# SomTest1.net
KiCad netlist of a schematic drawn in EAGLE
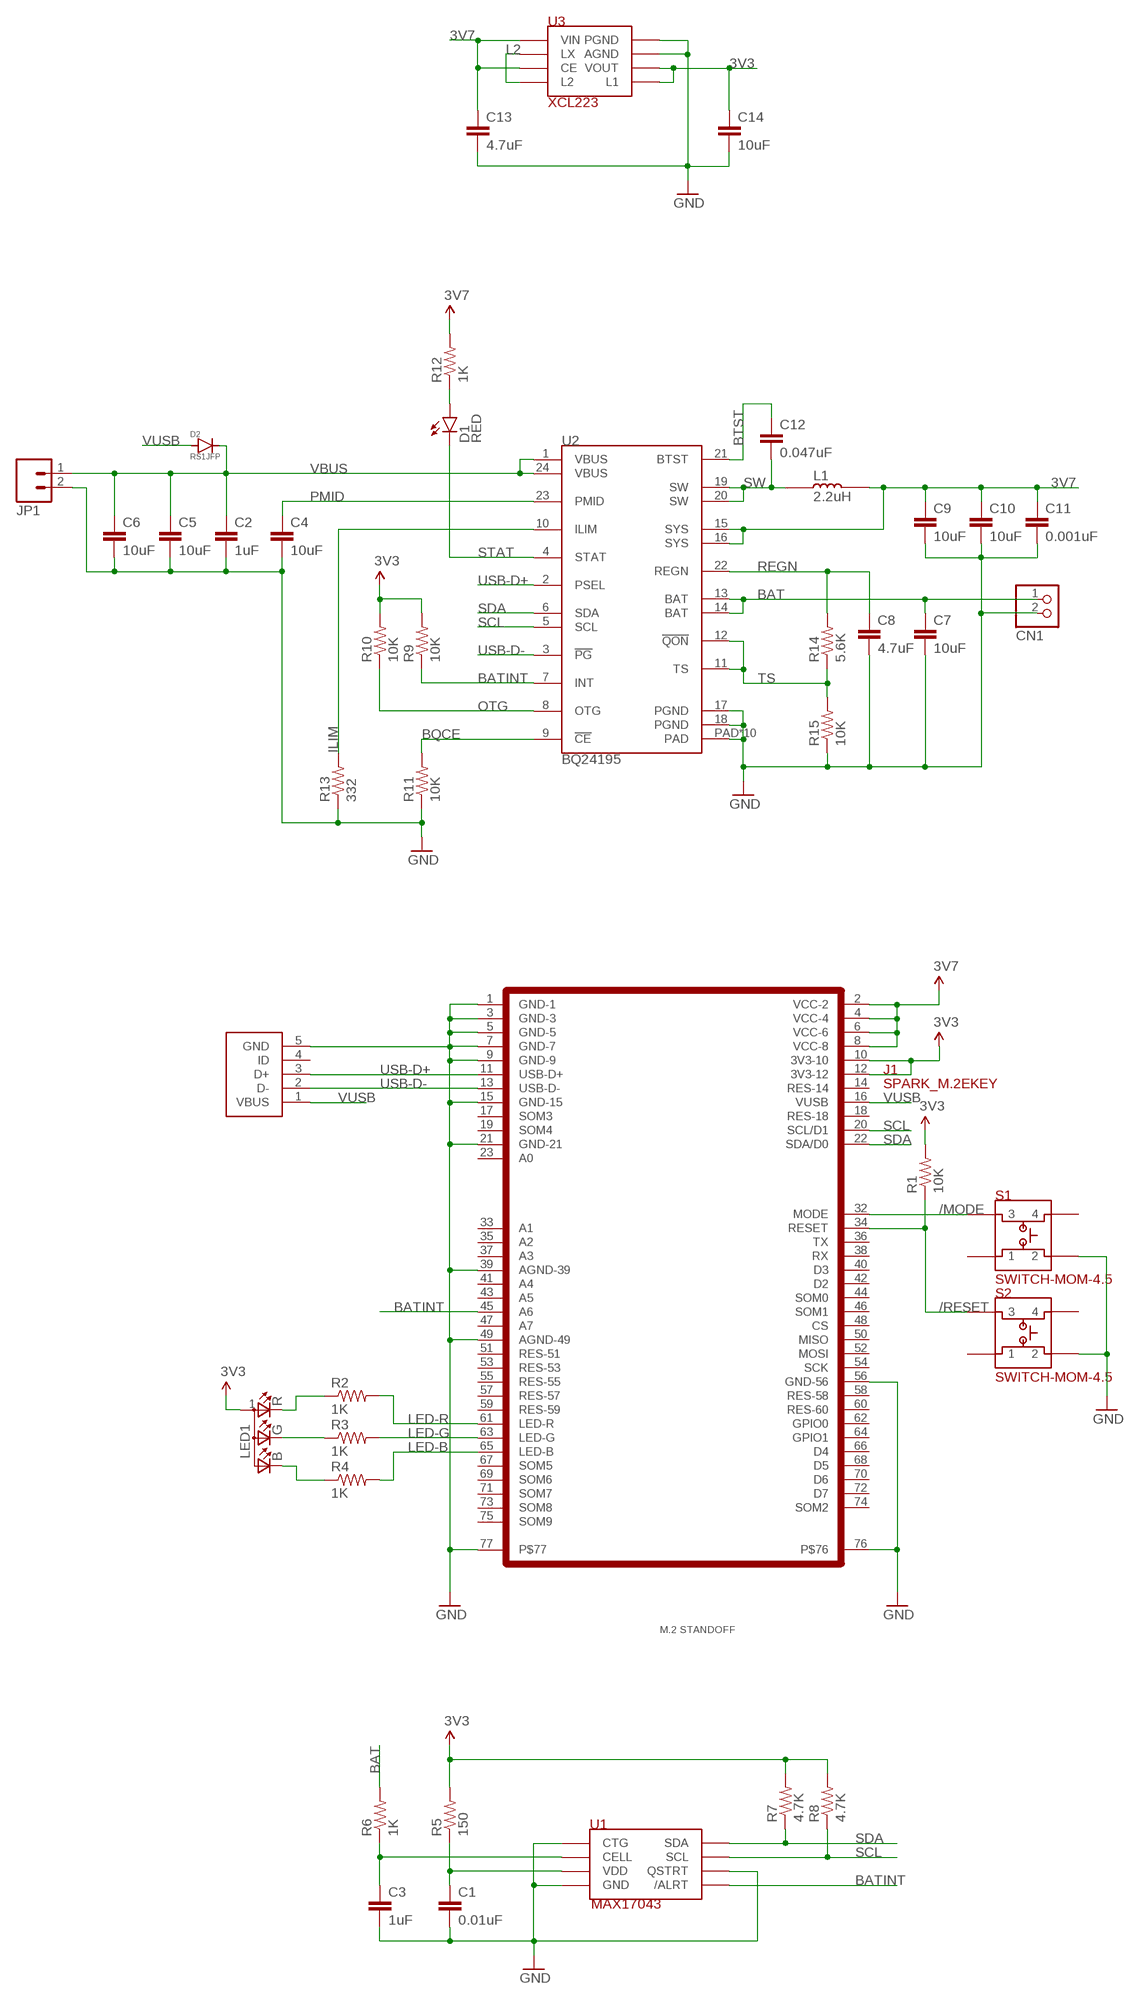
[diagram p0: schematic, sheet 1]

(export (version "E")
  (design (tool "Eeschema 10.0.6"))
  (components
    (comp (ref "C1")
      (value "0.01uF")
      (footprint "eagle-import:0603-CAP")
      (libsource (lib "eagle-import") (part "CAP-0.01UF-0603"))
    )
    (comp (ref "C2")
      (value "1uF")
      (footprint "eagle-import:0603-CAP")
      (libsource (lib "eagle-import") (part "CAP-1UF-0603.DEV"))
    )
    (comp (ref "C3")
      (value "1uF")
      (footprint "eagle-import:0603-CAP")
      (libsource (lib "eagle-import") (part "CAP-1UF-0603.DEV"))
    )
    (comp (ref "C4")
      (value "10uF")
      (footprint "eagle-import:0603-CAP")
      (libsource (lib "eagle-import") (part "CAP-10UF-0603"))
    )
    (comp (ref "C5")
      (value "10uF")
      (footprint "eagle-import:0603-CAP")
      (libsource (lib "eagle-import") (part "CAP-10UF-0603"))
    )
    (comp (ref "C6")
      (value "10uF")
      (footprint "eagle-import:0603-CAP")
      (libsource (lib "eagle-import") (part "CAP-10UF-0603"))
    )
    (comp (ref "C7")
      (value "10uF")
      (footprint "eagle-import:0603-CAP")
      (libsource (lib "eagle-import") (part "CAP-10UF-0603"))
    )
    (comp (ref "C8")
      (value "4.7uF")
      (footprint "eagle-import:0603-CAP")
      (libsource (lib "eagle-import") (part "CAP-4.7UF-0603"))
    )
    (comp (ref "C9")
      (value "10uF")
      (footprint "eagle-import:0603-CAP")
      (libsource (lib "eagle-import") (part "CAP-10UF-0603"))
    )
    (comp (ref "C10")
      (value "10uF")
      (footprint "eagle-import:0603-CAP")
      (libsource (lib "eagle-import") (part "CAP-10UF-0603"))
    )
    (comp (ref "C11")
      (value "0.001uF")
      (footprint "eagle-import:0603-CAP")
      (libsource (lib "eagle-import") (part "CAP-0.001UF-0603"))
    )
    (comp (ref "C12")
      (value "0.047uF")
      (footprint "eagle-import:0603-CAP")
      (libsource (lib "eagle-import") (part "CAP-0.047UF-0603"))
    )
    (comp (ref "C13")
      (value "4.7uF")
      (footprint "eagle-import:0603-CAP")
      (libsource (lib "eagle-import") (part "CAP-4.7UF-0603"))
    )
    (comp (ref "C14")
      (value "10uF")
      (footprint "eagle-import:0603-CAP")
      (libsource (lib "eagle-import") (part "CAP-10UF-0603"))
    )
    (comp (ref "CN1")
      (value "JST_2PIN-THM")
      (footprint "eagle-import:JST-PH-2-THM")
      (libsource (lib "eagle-import") (part "JST_2PIN-THM"))
    )
    (comp (ref "D1")
      (value "RED")
      (footprint "eagle-import:LED-0603")
      (libsource (lib "eagle-import") (part "LED-RED"))
    )
    (comp (ref "D2")
      (value "RS1JFP")
      (footprint "eagle-import:SOD-123HE-ON")
      (libsource (lib "eagle-import") (part "DIODE-RS1JFP"))
    )
    (comp (ref "J1")
      (value "SPARK_M.2EKEY")
      (footprint "eagle-import:SPARK_M.2EKEY-LESS-CREAM")
      (libsource (lib "eagle-import") (part "SPARK_M.2EKEY"))
    )
    (comp (ref "JP1")
      (value "M02PTH")
      (footprint "eagle-import:1X02")
      (libsource (lib "eagle-import") (part "M02PTH"))
    )
    (comp (ref "L1")
      (value "2.2uH")
      (footprint "eagle-import:1008-BOURNS")
      (libsource (lib "eagle-import") (part "INDUCTOR-2.2UH"))
    )
    (comp (ref "LED1")
      (value "LED-RGB-CREE-SMD")
      (footprint "eagle-import:LED-RGB-CREE-SMD")
      (libsource (lib "eagle-import") (part "LED-RGB-CREE-SMD"))
    )
    (comp (ref "R1")
      (value "10K")
      (footprint "eagle-import:0603-RES")
      (libsource (lib "eagle-import") (part "RES-10K-06030603"))
    )
    (comp (ref "R2")
      (value "1K")
      (footprint "eagle-import:0603-RES")
      (libsource (lib "eagle-import") (part "RES-1K-0603"))
    )
    (comp (ref "R3")
      (value "1K")
      (footprint "eagle-import:0603-RES")
      (libsource (lib "eagle-import") (part "RES-1K-0603"))
    )
    (comp (ref "R4")
      (value "1K")
      (footprint "eagle-import:0603-RES")
      (libsource (lib "eagle-import") (part "RES-1K-0603"))
    )
    (comp (ref "R5")
      (value "150")
      (footprint "eagle-import:0603-RES")
      (libsource (lib "eagle-import") (part "RES-150-0603"))
    )
    (comp (ref "R6")
      (value "1K")
      (footprint "eagle-import:0603-RES")
      (libsource (lib "eagle-import") (part "RES-1K-0603"))
    )
    (comp (ref "R7")
      (value "4.7K")
      (footprint "eagle-import:0603-RES")
      (libsource (lib "eagle-import") (part "RES-4.7K-0603"))
    )
    (comp (ref "R8")
      (value "4.7K")
      (footprint "eagle-import:0603-RES")
      (libsource (lib "eagle-import") (part "RES-4.7K-0603"))
    )
    (comp (ref "R9")
      (value "10K")
      (footprint "eagle-import:0603-RES")
      (libsource (lib "eagle-import") (part "RES-10K-06030603"))
    )
    (comp (ref "R10")
      (value "10K")
      (footprint "eagle-import:0603-RES")
      (libsource (lib "eagle-import") (part "RES-10K-06030603"))
    )
    (comp (ref "R11")
      (value "10K")
      (footprint "eagle-import:0603-RES")
      (libsource (lib "eagle-import") (part "RES-10K-06030603"))
    )
    (comp (ref "R12")
      (value "1K")
      (footprint "eagle-import:0603-RES")
      (libsource (lib "eagle-import") (part "RES-1K-0603"))
    )
    (comp (ref "R13")
      (value "332")
      (footprint "eagle-import:0603-RES")
      (libsource (lib "eagle-import") (part "RES-332-0603.DEV"))
    )
    (comp (ref "R14")
      (value "5.6K")
      (footprint "eagle-import:0603-RES")
      (libsource (lib "eagle-import") (part "RES-5.6K-0603"))
    )
    (comp (ref "R15")
      (value "10K")
      (footprint "eagle-import:0603-RES")
      (libsource (lib "eagle-import") (part "RES-10K-06030603"))
    )
    (comp (ref "S1")
      (value "SWITCH-MOM-4.5")
      (footprint "eagle-import:SWITCH-MOM-4.5")
      (libsource (lib "eagle-import") (part "SWITCH-MOM-4.5"))
    )
    (comp (ref "S2")
      (value "SWITCH-MOM-4.5")
      (footprint "eagle-import:SWITCH-MOM-4.5")
      (libsource (lib "eagle-import") (part "SWITCH-MOM-4.5"))
    )
    (comp (ref "U$1")
      (value "M2-STANDOFF")
      (footprint "eagle-import:M2-STANDOFF")
      (libsource (lib "eagle-import") (part "M2-STANDOFF"))
    )
    (comp (ref "U$3")
      (value "USB-MICRO-B-SOCKET-AMPHENOL")
      (footprint "eagle-import:USB-B-SMT-AMPHENOL")
      (libsource (lib "eagle-import") (part "USB-MICRO-B-SOCKET-AMPHENOL"))
    )
    (comp (ref "U1")
      (value "MAX17043")
      (footprint "eagle-import:9UCSP-MAXIM")
      (libsource (lib "eagle-import") (part "MAX17043"))
    )
    (comp (ref "U2")
      (value "BQ24195")
      (footprint "eagle-import:24VFQN-TI")
      (libsource (lib "eagle-import") (part "BQ24195"))
    )
    (comp (ref "U3")
      (value "XCL223")
      (footprint "eagle-import:REG-XCL223-LESS-CREAM")
      (libsource (lib "eagle-import") (part "REG-XCL223"))
    )
  )
  (nets
    (net (code "1") (name "/BAT") (class "Default")
      (node (ref "C7") (pin "1") (pinfunction "1_1") (pintype "passive"))
      (node (ref "CN1") (pin "1") (pinfunction "2_1") (pintype "passive"))
      (node (ref "R6") (pin "2") (pinfunction "2_2") (pintype "passive"))
      (node (ref "U2") (pin "13") (pinfunction "BAT_13") (pintype "passive"))
      (node (ref "U2") (pin "14") (pinfunction "BAT_14") (pintype "power_in"))
    )
    (net (code "2") (name "/BATINT") (class "Default")
      (node (ref "J1") (pin "45") (pinfunction "A6_45") (pintype "bidirectional"))
      (node (ref "R9") (pin "1") (pinfunction "1_1") (pintype "passive"))
      (node (ref "U1") (pin "C1") (pinfunction "/ALRT_C1") (pintype "output"))
      (node (ref "U2") (pin "7") (pinfunction "INT_7") (pintype "bidirectional"))
    )
    (net (code "3") (name "/BQCE") (class "Default")
      (node (ref "R11") (pin "2") (pinfunction "2_2") (pintype "passive"))
      (node (ref "U2") (pin "9") (pinfunction "~{CE}_9") (pintype "output"))
    )
    (net (code "4") (name "/BTST") (class "Default")
      (node (ref "C12") (pin "1") (pinfunction "1_1") (pintype "passive"))
      (node (ref "U2") (pin "21") (pinfunction "BTST_21") (pintype "bidirectional"))
    )
    (net (code "5") (name "/ILIM") (class "Default")
      (node (ref "R13") (pin "2") (pinfunction "2_2") (pintype "passive"))
      (node (ref "U2") (pin "10") (pinfunction "ILIM_10") (pintype "output"))
    )
    (net (code "6") (name "/L2") (class "Default")
      (node (ref "U3") (pin "5") (pinfunction "LX_5") (pintype "passive"))
      (node (ref "U3") (pin "8") (pinfunction "L2_8") (pintype "passive"))
    )
    (net (code "7") (name "/LED-B") (class "Default")
      (node (ref "J1") (pin "65") (pinfunction "LED-B_65") (pintype "bidirectional"))
      (node (ref "R4") (pin "2") (pinfunction "2_2") (pintype "passive"))
    )
    (net (code "8") (name "/LED-G") (class "Default")
      (node (ref "J1") (pin "63") (pinfunction "LED-G_63") (pintype "bidirectional"))
      (node (ref "R3") (pin "2") (pinfunction "2_2") (pintype "passive"))
    )
    (net (code "9") (name "/LED-R") (class "Default")
      (node (ref "J1") (pin "61") (pinfunction "LED-R_61") (pintype "bidirectional"))
      (node (ref "R2") (pin "2") (pinfunction "2_2") (pintype "passive"))
    )
    (net (code "10") (name "/OTG") (class "Default")
      (node (ref "R10") (pin "1") (pinfunction "1_1") (pintype "passive"))
      (node (ref "U2") (pin "8") (pinfunction "OTG_8") (pintype "bidirectional"))
    )
    (net (code "11") (name "/PMID") (class "Default")
      (node (ref "C4") (pin "1") (pinfunction "1_1") (pintype "passive"))
      (node (ref "U2") (pin "23") (pinfunction "PMID_23") (pintype "passive"))
    )
    (net (code "12") (name "/REGN") (class "Default")
      (node (ref "C8") (pin "1") (pinfunction "1_1") (pintype "passive"))
      (node (ref "R14") (pin "2") (pinfunction "2_2") (pintype "passive"))
      (node (ref "U2") (pin "22") (pinfunction "REGN_22") (pintype "bidirectional"))
    )
    (net (code "13") (name "/SCL") (class "Default")
      (node (ref "J1") (pin "20") (pinfunction "SCL/D1_20") (pintype "bidirectional"))
      (node (ref "R8") (pin "1") (pinfunction "1_1") (pintype "passive"))
      (node (ref "U1") (pin "A2") (pinfunction "SCL_A2") (pintype "bidirectional"))
      (node (ref "U2") (pin "5") (pinfunction "SCL_5") (pintype "output"))
    )
    (net (code "14") (name "/SDA") (class "Default")
      (node (ref "J1") (pin "22") (pinfunction "SDA/D0_22") (pintype "bidirectional"))
      (node (ref "R7") (pin "1") (pinfunction "1_1") (pintype "passive"))
      (node (ref "U1") (pin "A1") (pinfunction "SDA_A1") (pintype "bidirectional"))
      (node (ref "U2") (pin "6") (pinfunction "SDA_6") (pintype "bidirectional"))
    )
    (net (code "15") (name "/STAT") (class "Default")
      (node (ref "D1") (pin "C") (pinfunction "C_C") (pintype "passive"))
      (node (ref "U2") (pin "4") (pinfunction "STAT_4") (pintype "bidirectional"))
    )
    (net (code "16") (name "/SW") (class "Default")
      (node (ref "C12") (pin "2") (pinfunction "2_2") (pintype "passive"))
      (node (ref "L1") (pin "1") (pinfunction "P$1_1") (pintype "passive"))
      (node (ref "U2") (pin "19") (pinfunction "SW_19") (pintype "power_in"))
      (node (ref "U2") (pin "20") (pinfunction "SW_20") (pintype "power_in"))
    )
    (net (code "17") (name "/TS") (class "Default")
      (node (ref "R14") (pin "1") (pinfunction "1_1") (pintype "passive"))
      (node (ref "R15") (pin "2") (pinfunction "2_2") (pintype "passive"))
      (node (ref "U2") (pin "11") (pinfunction "TS_11") (pintype "bidirectional"))
      (node (ref "U2") (pin "12") (pinfunction "~{QON}_12") (pintype "bidirectional"))
    )
    (net (code "18") (name "/USB-D+") (class "Default")
      (node (ref "J1") (pin "11") (pinfunction "USB-D+_11") (pintype "bidirectional"))
      (node (ref "U$3") (pin "3") (pinfunction "D+_3") (pintype "passive"))
      (node (ref "U2") (pin "2") (pinfunction "PSEL_2") (pintype "output"))
    )
    (net (code "19") (name "/USB-D-") (class "Default")
      (node (ref "J1") (pin "13") (pinfunction "USB-D-_13") (pintype "bidirectional"))
      (node (ref "U$3") (pin "2") (pinfunction "D-_2") (pintype "passive"))
      (node (ref "U2") (pin "3") (pinfunction "~{PG}_3") (pintype "output"))
    )
    (net (code "20") (name "/VBUS") (class "Default")
      (node (ref "C2") (pin "1") (pinfunction "1_1") (pintype "passive"))
      (node (ref "C5") (pin "1") (pinfunction "1_1") (pintype "passive"))
      (node (ref "C6") (pin "1") (pinfunction "1_1") (pintype "passive"))
      (node (ref "D2") (pin "1") (pinfunction "CATHODE_1") (pintype "bidirectional"))
      (node (ref "JP1") (pin "1") (pinfunction "1_1") (pintype "passive"))
      (node (ref "U2") (pin "1") (pinfunction "VBUS_1") (pintype "power_in"))
      (node (ref "U2") (pin "24") (pinfunction "VBUS_24") (pintype "passive"))
    )
    (net (code "21") (name "/VUSB") (class "Default")
      (node (ref "D2") (pin "2") (pinfunction "ANODE_2") (pintype "bidirectional"))
      (node (ref "J1") (pin "16") (pinfunction "VUSB_16") (pintype "bidirectional"))
      (node (ref "U$3") (pin "1") (pinfunction "VBUS_1") (pintype "passive"))
    )
    (net (code "22") (name "/{slash}MODE") (class "Default")
      (node (ref "J1") (pin "32") (pinfunction "MODE_32") (pintype "bidirectional"))
      (node (ref "S1") (pin "3") (pinfunction "3_3") (pintype "passive"))
    )
    (net (code "23") (name "/{slash}RESET") (class "Default")
      (node (ref "J1") (pin "34") (pinfunction "RESET_34") (pintype "bidirectional"))
      (node (ref "R1") (pin "1") (pinfunction "1_1") (pintype "passive"))
      (node (ref "S2") (pin "3") (pinfunction "3_3") (pintype "passive"))
    )
    (net (code "24") (name "3V3") (class "Default")
      (node (ref "C14") (pin "1") (pinfunction "1_1") (pintype "passive"))
      (node (ref "J1") (pin "10") (pinfunction "3V3-10_10") (pintype "bidirectional"))
      (node (ref "J1") (pin "12") (pinfunction "3V3-12_12") (pintype "bidirectional"))
      (node (ref "LED1") (pin "1") (pinfunction "A_1") (pintype "passive"))
      (node (ref "R1") (pin "2") (pinfunction "2_2") (pintype "passive"))
      (node (ref "R10") (pin "2") (pinfunction "2_2") (pintype "passive"))
      (node (ref "R5") (pin "2") (pinfunction "2_2") (pintype "passive"))
      (node (ref "R7") (pin "2") (pinfunction "2_2") (pintype "passive"))
      (node (ref "R8") (pin "2") (pinfunction "2_2") (pintype "passive"))
      (node (ref "R9") (pin "2") (pinfunction "2_2") (pintype "passive"))
      (node (ref "U3") (pin "3") (pinfunction "VOUT_3") (pintype "passive"))
      (node (ref "U3") (pin "7") (pinfunction "L1_7") (pintype "passive"))
    )
    (net (code "25") (name "3V7") (class "Default")
      (node (ref "C10") (pin "1") (pinfunction "1_1") (pintype "passive"))
      (node (ref "C11") (pin "1") (pinfunction "1_1") (pintype "passive"))
      (node (ref "C13") (pin "1") (pinfunction "1_1") (pintype "passive"))
      (node (ref "C9") (pin "1") (pinfunction "1_1") (pintype "passive"))
      (node (ref "J1") (pin "2") (pinfunction "VCC-2_2") (pintype "bidirectional"))
      (node (ref "J1") (pin "4") (pinfunction "VCC-4_4") (pintype "bidirectional"))
      (node (ref "J1") (pin "6") (pinfunction "VCC-6_6") (pintype "bidirectional"))
      (node (ref "J1") (pin "8") (pinfunction "VCC-8_8") (pintype "bidirectional"))
      (node (ref "L1") (pin "2") (pinfunction "P$2_2") (pintype "passive"))
      (node (ref "R12") (pin "2") (pinfunction "2_2") (pintype "passive"))
      (node (ref "U2") (pin "15") (pinfunction "SYS_15") (pintype "power_in"))
      (node (ref "U2") (pin "16") (pinfunction "SYS_16") (pintype "power_in"))
      (node (ref "U3") (pin "4") (pinfunction "CE_4") (pintype "input"))
      (node (ref "U3") (pin "6") (pinfunction "VIN_6") (pintype "power_in"))
    )
    (net (code "26") (name "GND") (class "Default")
      (node (ref "C1") (pin "2") (pinfunction "2_2") (pintype "passive"))
      (node (ref "C10") (pin "2") (pinfunction "2_2") (pintype "passive"))
      (node (ref "C11") (pin "2") (pinfunction "2_2") (pintype "passive"))
      (node (ref "C13") (pin "2") (pinfunction "2_2") (pintype "passive"))
      (node (ref "C14") (pin "2") (pinfunction "2_2") (pintype "passive"))
      (node (ref "C2") (pin "2") (pinfunction "2_2") (pintype "passive"))
      (node (ref "C3") (pin "2") (pinfunction "2_2") (pintype "passive"))
      (node (ref "C4") (pin "2") (pinfunction "2_2") (pintype "passive"))
      (node (ref "C5") (pin "2") (pinfunction "2_2") (pintype "passive"))
      (node (ref "C6") (pin "2") (pinfunction "2_2") (pintype "passive"))
      (node (ref "C7") (pin "2") (pinfunction "2_2") (pintype "passive"))
      (node (ref "C8") (pin "2") (pinfunction "2_2") (pintype "passive"))
      (node (ref "C9") (pin "2") (pinfunction "2_2") (pintype "passive"))
      (node (ref "CN1") (pin "2") (pinfunction "1_2") (pintype "passive"))
      (node (ref "J1") (pin "1") (pinfunction "GND-1_1") (pintype "bidirectional"))
      (node (ref "J1") (pin "15") (pinfunction "GND-15_15") (pintype "bidirectional"))
      (node (ref "J1") (pin "21") (pinfunction "GND-21_21") (pintype "bidirectional"))
      (node (ref "J1") (pin "3") (pinfunction "GND-3_3") (pintype "bidirectional"))
      (node (ref "J1") (pin "39") (pinfunction "AGND-39_39") (pintype "bidirectional"))
      (node (ref "J1") (pin "49") (pinfunction "AGND-49_49") (pintype "bidirectional"))
      (node (ref "J1") (pin "5") (pinfunction "GND-5_5") (pintype "bidirectional"))
      (node (ref "J1") (pin "56") (pinfunction "GND-56_56") (pintype "bidirectional"))
      (node (ref "J1") (pin "7") (pinfunction "GND-7_7") (pintype "bidirectional"))
      (node (ref "J1") (pin "76") (pinfunction "P$76_76") (pintype "power_in"))
      (node (ref "J1") (pin "77") (pinfunction "P$77_77") (pintype "power_in"))
      (node (ref "J1") (pin "9") (pinfunction "GND-9_9") (pintype "bidirectional"))
      (node (ref "JP1") (pin "2") (pinfunction "2_2") (pintype "passive"))
      (node (ref "R11") (pin "1") (pinfunction "1_1") (pintype "passive"))
      (node (ref "R13") (pin "1") (pinfunction "1_1") (pintype "passive"))
      (node (ref "R15") (pin "1") (pinfunction "1_1") (pintype "passive"))
      (node (ref "S1") (pin "2") (pinfunction "2_2") (pintype "passive"))
      (node (ref "S2") (pin "2") (pinfunction "2_2") (pintype "passive"))
      (node (ref "U$3") (pin "5") (pinfunction "GND_5") (pintype "passive"))
      (node (ref "U1") (pin "A3") (pinfunction "CTG_A3") (pintype "power_in"))
      (node (ref "U1") (pin "B1") (pinfunction "QSTRT_B1") (pintype "input"))
      (node (ref "U1") (pin "C3") (pinfunction "GND_C3") (pintype "power_in"))
      (node (ref "U2") (pin "17") (pinfunction "PGND_17") (pintype "passive"))
      (node (ref "U2") (pin "18") (pinfunction "PGND_18") (pintype "passive"))
      (node (ref "U2") (pin "PAD") (pinfunction "PAD_PAD") (pintype "power_in"))
      (node (ref "U2") (pin "PAD@1") (pinfunction "PAD_PAD@1") (pintype "power_in"))
      (node (ref "U2") (pin "PAD@2") (pinfunction "PAD_PAD@2") (pintype "power_in"))
      (node (ref "U2") (pin "PAD@3") (pinfunction "PAD_PAD@3") (pintype "power_in"))
      (node (ref "U2") (pin "PAD@4") (pinfunction "PAD_PAD@4") (pintype "power_in"))
      (node (ref "U2") (pin "PAD@5") (pinfunction "PAD_PAD@5") (pintype "power_in"))
      (node (ref "U2") (pin "PAD@6") (pinfunction "PAD_PAD@6") (pintype "power_in"))
      (node (ref "U2") (pin "PAD@7") (pinfunction "PAD_PAD@7") (pintype "power_in"))
      (node (ref "U2") (pin "PAD@8") (pinfunction "PAD_PAD@8") (pintype "power_in"))
      (node (ref "U2") (pin "PAD@9") (pinfunction "PAD_PAD@9") (pintype "power_in"))
      (node (ref "U3") (pin "1") (pinfunction "PGND_1") (pintype "passive"))
      (node (ref "U3") (pin "2") (pinfunction "AGND_2") (pintype "passive"))
    )
    (net (code "27") (name "Net-(D1-PadA)") (class "Default")
      (node (ref "D1") (pin "A") (pinfunction "A_A") (pintype "passive"))
      (node (ref "R12") (pin "1") (pinfunction "1_1") (pintype "passive"))
    )
    (net (code "28") (name "Net-(LED1-B)") (class "Default")
      (node (ref "LED1") (pin "2") (pinfunction "B_2") (pintype "passive"))
      (node (ref "R4") (pin "1") (pinfunction "1_1") (pintype "passive"))
    )
    (net (code "29") (name "Net-(LED1-G)") (class "Default")
      (node (ref "LED1") (pin "3") (pinfunction "G_3") (pintype "passive"))
      (node (ref "R3") (pin "1") (pinfunction "1_1") (pintype "passive"))
    )
    (net (code "30") (name "Net-(LED1-R)") (class "Default")
      (node (ref "LED1") (pin "4") (pinfunction "R_4") (pintype "passive"))
      (node (ref "R2") (pin "1") (pinfunction "1_1") (pintype "passive"))
    )
    (net (code "31") (name "Net-(U1-CELL)") (class "Default")
      (node (ref "C3") (pin "1") (pinfunction "1_1") (pintype "passive"))
      (node (ref "R6") (pin "1") (pinfunction "1_1") (pintype "passive"))
      (node (ref "U1") (pin "B3") (pinfunction "CELL_B3") (pintype "power_in"))
    )
    (net (code "32") (name "Net-(U1-VDD)") (class "Default")
      (node (ref "C1") (pin "1") (pinfunction "1_1") (pintype "passive"))
      (node (ref "R5") (pin "1") (pinfunction "1_1") (pintype "passive"))
      (node (ref "U1") (pin "C2") (pinfunction "VDD_C2") (pintype "power_in"))
    )
    (net (code "33") (name "unconnected-(J1-A0-Pad23)") (class "Default")
      (node (ref "J1") (pin "23") (pinfunction "A0_23") (pintype "bidirectional"))
    )
    (net (code "34") (name "unconnected-(J1-A1-Pad33)") (class "Default")
      (node (ref "J1") (pin "33") (pinfunction "A1_33") (pintype "bidirectional"))
    )
    (net (code "35") (name "unconnected-(J1-A2-Pad35)") (class "Default")
      (node (ref "J1") (pin "35") (pinfunction "A2_35") (pintype "bidirectional"))
    )
    (net (code "36") (name "unconnected-(J1-A3-Pad37)") (class "Default")
      (node (ref "J1") (pin "37") (pinfunction "A3_37") (pintype "bidirectional"))
    )
    (net (code "37") (name "unconnected-(J1-A4-Pad41)") (class "Default")
      (node (ref "J1") (pin "41") (pinfunction "A4_41") (pintype "bidirectional"))
    )
    (net (code "38") (name "unconnected-(J1-A5-Pad43)") (class "Default")
      (node (ref "J1") (pin "43") (pinfunction "A5_43") (pintype "bidirectional"))
    )
    (net (code "39") (name "unconnected-(J1-A7-Pad47)") (class "Default")
      (node (ref "J1") (pin "47") (pinfunction "A7_47") (pintype "bidirectional"))
    )
    (net (code "40") (name "unconnected-(J1-CS-Pad48)") (class "Default")
      (node (ref "J1") (pin "48") (pinfunction "CS_48") (pintype "bidirectional"))
    )
    (net (code "41") (name "unconnected-(J1-D2-Pad42)") (class "Default")
      (node (ref "J1") (pin "42") (pinfunction "D2_42") (pintype "bidirectional"))
    )
    (net (code "42") (name "unconnected-(J1-D3-Pad40)") (class "Default")
      (node (ref "J1") (pin "40") (pinfunction "D3_40") (pintype "bidirectional"))
    )
    (net (code "43") (name "unconnected-(J1-D4-Pad66)") (class "Default")
      (node (ref "J1") (pin "66") (pinfunction "D4_66") (pintype "bidirectional"))
    )
    (net (code "44") (name "unconnected-(J1-D5-Pad68)") (class "Default")
      (node (ref "J1") (pin "68") (pinfunction "D5_68") (pintype "bidirectional"))
    )
    (net (code "45") (name "unconnected-(J1-D6-Pad70)") (class "Default")
      (node (ref "J1") (pin "70") (pinfunction "D6_70") (pintype "bidirectional"))
    )
    (net (code "46") (name "unconnected-(J1-D7-Pad72)") (class "Default")
      (node (ref "J1") (pin "72") (pinfunction "D7_72") (pintype "bidirectional"))
    )
    (net (code "47") (name "unconnected-(J1-GPIO0-Pad62)") (class "Default")
      (node (ref "J1") (pin "62") (pinfunction "GPIO0_62") (pintype "bidirectional"))
    )
    (net (code "48") (name "unconnected-(J1-GPIO1-Pad64)") (class "Default")
      (node (ref "J1") (pin "64") (pinfunction "GPIO1_64") (pintype "bidirectional"))
    )
    (net (code "49") (name "unconnected-(J1-MISO-Pad50)") (class "Default")
      (node (ref "J1") (pin "50") (pinfunction "MISO_50") (pintype "bidirectional"))
    )
    (net (code "50") (name "unconnected-(J1-MOSI-Pad52)") (class "Default")
      (node (ref "J1") (pin "52") (pinfunction "MOSI_52") (pintype "bidirectional"))
    )
    (net (code "51") (name "unconnected-(J1-RES-14-Pad14)") (class "Default")
      (node (ref "J1") (pin "14") (pinfunction "RES-14_14") (pintype "bidirectional"))
    )
    (net (code "52") (name "unconnected-(J1-RES-18-Pad18)") (class "Default")
      (node (ref "J1") (pin "18") (pinfunction "RES-18_18") (pintype "bidirectional"))
    )
    (net (code "53") (name "unconnected-(J1-RES-51-Pad51)") (class "Default")
      (node (ref "J1") (pin "51") (pinfunction "RES-51_51") (pintype "bidirectional"))
    )
    (net (code "54") (name "unconnected-(J1-RES-53-Pad53)") (class "Default")
      (node (ref "J1") (pin "53") (pinfunction "RES-53_53") (pintype "bidirectional"))
    )
    (net (code "55") (name "unconnected-(J1-RES-55-Pad55)") (class "Default")
      (node (ref "J1") (pin "55") (pinfunction "RES-55_55") (pintype "bidirectional"))
    )
    (net (code "56") (name "unconnected-(J1-RES-57-Pad57)") (class "Default")
      (node (ref "J1") (pin "57") (pinfunction "RES-57_57") (pintype "bidirectional"))
    )
    (net (code "57") (name "unconnected-(J1-RES-58-Pad58)") (class "Default")
      (node (ref "J1") (pin "58") (pinfunction "RES-58_58") (pintype "bidirectional"))
    )
    (net (code "58") (name "unconnected-(J1-RES-59-Pad59)") (class "Default")
      (node (ref "J1") (pin "59") (pinfunction "RES-59_59") (pintype "bidirectional"))
    )
    (net (code "59") (name "unconnected-(J1-RES-60-Pad60)") (class "Default")
      (node (ref "J1") (pin "60") (pinfunction "RES-60_60") (pintype "bidirectional"))
    )
    (net (code "60") (name "unconnected-(J1-RX-Pad38)") (class "Default")
      (node (ref "J1") (pin "38") (pinfunction "RX_38") (pintype "bidirectional"))
    )
    (net (code "61") (name "unconnected-(J1-SCK-Pad54)") (class "Default")
      (node (ref "J1") (pin "54") (pinfunction "SCK_54") (pintype "bidirectional"))
    )
    (net (code "62") (name "unconnected-(J1-SOM0-Pad44)") (class "Default")
      (node (ref "J1") (pin "44") (pinfunction "SOM0_44") (pintype "bidirectional"))
    )
    (net (code "63") (name "unconnected-(J1-SOM1-Pad46)") (class "Default")
      (node (ref "J1") (pin "46") (pinfunction "SOM1_46") (pintype "bidirectional"))
    )
    (net (code "64") (name "unconnected-(J1-SOM2-Pad74)") (class "Default")
      (node (ref "J1") (pin "74") (pinfunction "SOM2_74") (pintype "bidirectional"))
    )
    (net (code "65") (name "unconnected-(J1-SOM3-Pad17)") (class "Default")
      (node (ref "J1") (pin "17") (pinfunction "SOM3_17") (pintype "bidirectional"))
    )
    (net (code "66") (name "unconnected-(J1-SOM4-Pad19)") (class "Default")
      (node (ref "J1") (pin "19") (pinfunction "SOM4_19") (pintype "bidirectional"))
    )
    (net (code "67") (name "unconnected-(J1-SOM5-Pad67)") (class "Default")
      (node (ref "J1") (pin "67") (pinfunction "SOM5_67") (pintype "bidirectional"))
    )
    (net (code "68") (name "unconnected-(J1-SOM6-Pad69)") (class "Default")
      (node (ref "J1") (pin "69") (pinfunction "SOM6_69") (pintype "bidirectional"))
    )
    (net (code "69") (name "unconnected-(J1-SOM7-Pad71)") (class "Default")
      (node (ref "J1") (pin "71") (pinfunction "SOM7_71") (pintype "bidirectional"))
    )
    (net (code "70") (name "unconnected-(J1-SOM8-Pad73)") (class "Default")
      (node (ref "J1") (pin "73") (pinfunction "SOM8_73") (pintype "bidirectional"))
    )
    (net (code "71") (name "unconnected-(J1-SOM9-Pad75)") (class "Default")
      (node (ref "J1") (pin "75") (pinfunction "SOM9_75") (pintype "bidirectional"))
    )
    (net (code "72") (name "unconnected-(J1-TX-Pad36)") (class "Default")
      (node (ref "J1") (pin "36") (pinfunction "TX_36") (pintype "bidirectional"))
    )
    (net (code "73") (name "unconnected-(S1-Pad1)") (class "Default")
      (node (ref "S1") (pin "1") (pinfunction "1_1") (pintype "passive"))
    )
    (net (code "74") (name "unconnected-(S1-Pad4)") (class "Default")
      (node (ref "S1") (pin "4") (pinfunction "4_4") (pintype "passive"))
    )
    (net (code "75") (name "unconnected-(S2-Pad1)") (class "Default")
      (node (ref "S2") (pin "1") (pinfunction "1_1") (pintype "passive"))
    )
    (net (code "76") (name "unconnected-(S2-Pad4)") (class "Default")
      (node (ref "S2") (pin "4") (pinfunction "4_4") (pintype "passive"))
    )
    (net (code "77") (name "unconnected-(U$3-ID-Pad4)") (class "Default")
      (node (ref "U$3") (pin "4") (pinfunction "ID_4") (pintype "passive"))
    )
  )
)
